# OPR5925Breakout.net
KiCad netlist of a schematic drawn in EAGLE
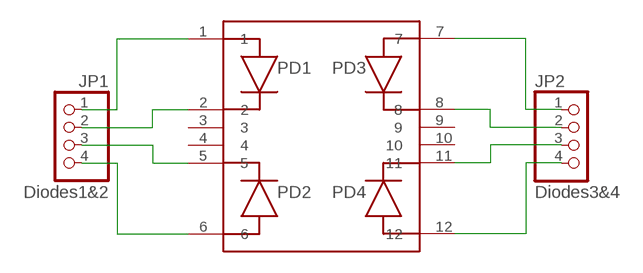
[diagram p0: schematic, sheet 1]

(export (version "E")
  (design (tool "Eeschema 10.0.6"))
  (components
    (comp (ref "JP1")
      (value "Diodes1&2")
      (footprint "eagle-import:1X04")
      (libsource (lib "eagle-import") (part "PINHD-1X4"))
    )
    (comp (ref "JP2")
      (value "Diodes3&4")
      (footprint "eagle-import:1X04")
      (libsource (lib "eagle-import") (part "PINHD-1X4"))
    )
    (comp (ref "U$1")
      (value "OPR5925")
      (footprint "eagle-import:OPR5925")
      (libsource (lib "eagle-import") (part "OPR5925"))
    )
  )
  (nets
    (net (code "1") (name "Net-(JP1-Pad1)") (class "Default")
      (node (ref "JP1") (pin "1") (pinfunction "1_1") (pintype "passive"))
      (node (ref "U$1") (pin "1") (pinfunction "1_1") (pintype "bidirectional"))
    )
    (net (code "2") (name "Net-(JP1-Pad2)") (class "Default")
      (node (ref "JP1") (pin "2") (pinfunction "2_2") (pintype "passive"))
      (node (ref "U$1") (pin "2") (pinfunction "2_2") (pintype "bidirectional"))
    )
    (net (code "3") (name "Net-(JP1-Pad3)") (class "Default")
      (node (ref "JP1") (pin "3") (pinfunction "3_3") (pintype "passive"))
      (node (ref "U$1") (pin "5") (pinfunction "5_5") (pintype "bidirectional"))
    )
    (net (code "4") (name "Net-(JP1-Pad4)") (class "Default")
      (node (ref "JP1") (pin "4") (pinfunction "4_4") (pintype "passive"))
      (node (ref "U$1") (pin "6") (pinfunction "6_6") (pintype "bidirectional"))
    )
    (net (code "5") (name "Net-(JP2-Pad1)") (class "Default")
      (node (ref "JP2") (pin "1") (pinfunction "1_1") (pintype "passive"))
      (node (ref "U$1") (pin "7") (pinfunction "7_7") (pintype "bidirectional"))
    )
    (net (code "6") (name "Net-(JP2-Pad2)") (class "Default")
      (node (ref "JP2") (pin "2") (pinfunction "2_2") (pintype "passive"))
      (node (ref "U$1") (pin "8") (pinfunction "8_8") (pintype "bidirectional"))
    )
    (net (code "7") (name "Net-(JP2-Pad3)") (class "Default")
      (node (ref "JP2") (pin "3") (pinfunction "3_3") (pintype "passive"))
      (node (ref "U$1") (pin "11") (pinfunction "11_11") (pintype "bidirectional"))
    )
    (net (code "8") (name "Net-(JP2-Pad4)") (class "Default")
      (node (ref "JP2") (pin "4") (pinfunction "4_4") (pintype "passive"))
      (node (ref "U$1") (pin "12") (pinfunction "12_12") (pintype "bidirectional"))
    )
    (net (code "9") (name "unconnected-(U$1-Pad3)") (class "Default")
      (node (ref "U$1") (pin "3") (pinfunction "3_3") (pintype "bidirectional"))
    )
    (net (code "10") (name "unconnected-(U$1-Pad4)") (class "Default")
      (node (ref "U$1") (pin "4") (pinfunction "4_4") (pintype "bidirectional"))
    )
    (net (code "11") (name "unconnected-(U$1-Pad9)") (class "Default")
      (node (ref "U$1") (pin "9") (pinfunction "9_9") (pintype "bidirectional"))
    )
    (net (code "12") (name "unconnected-(U$1-Pad10)") (class "Default")
      (node (ref "U$1") (pin "10") (pinfunction "10_10") (pintype "bidirectional"))
    )
  )
)
